# ESP32_Demo.net
KiCad netlist of a schematic drawn in Altium Designer
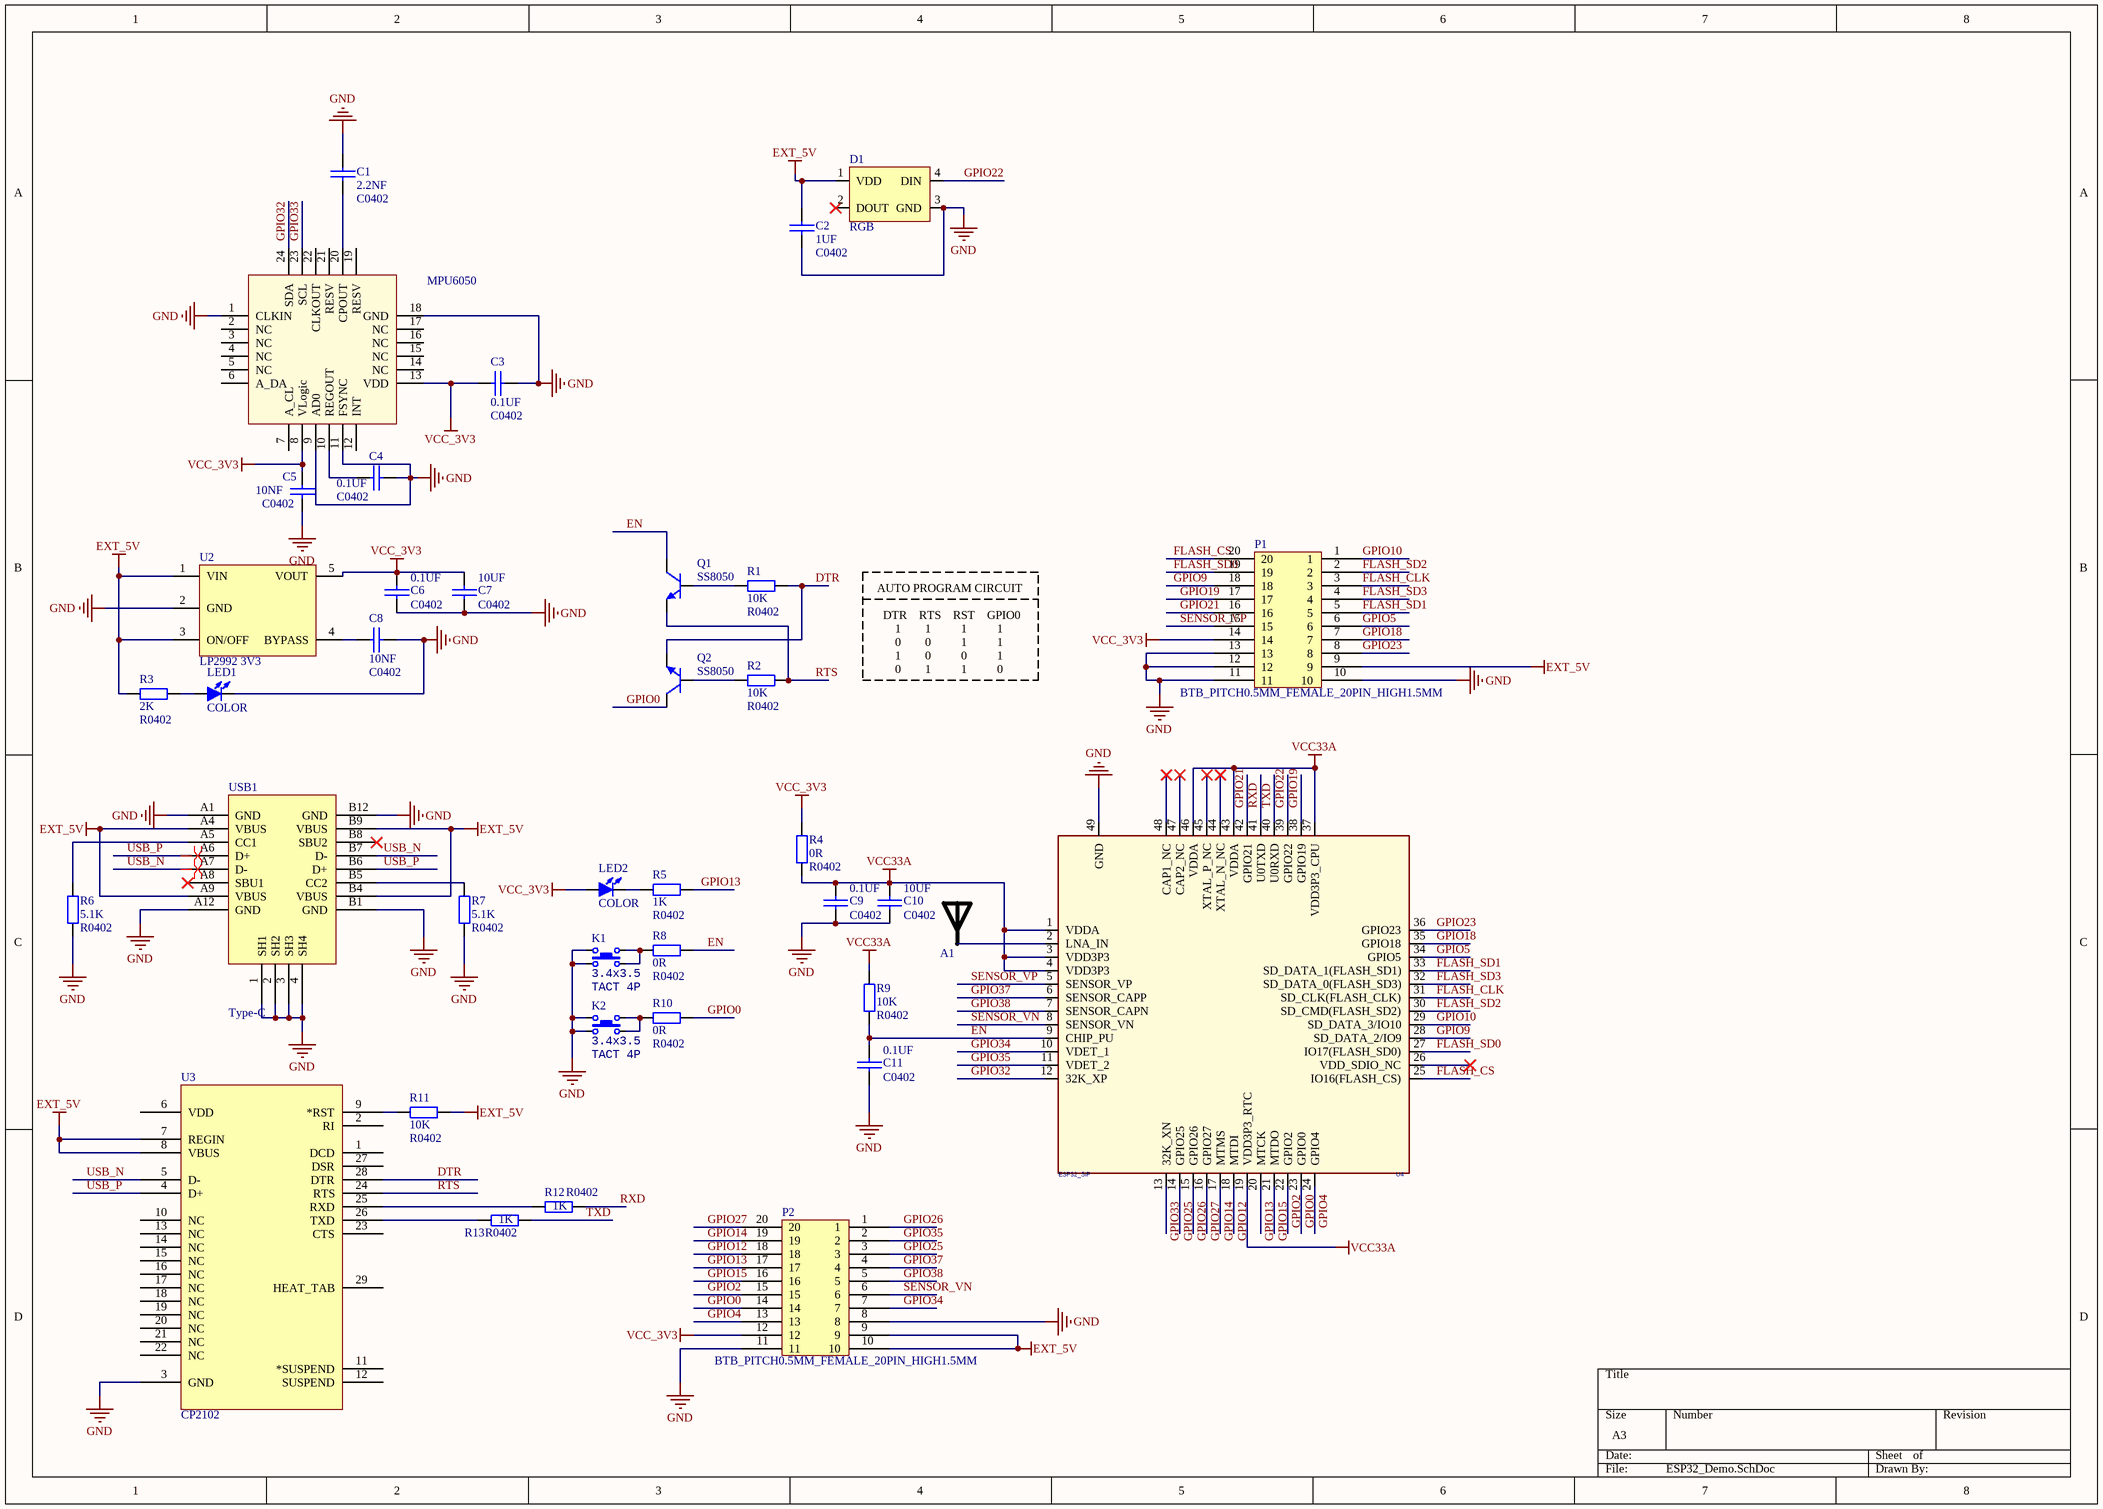
[diagram p0: ESP32_Demo.SchDoc]

(export (version "E")
  (design (tool "Eeschema 10.0.6"))
  (components
    (comp (ref "A1")
      (value "RAINSUN")
      (footprint "ANT-Rainsun-AN5120")
      (description "2.4GHz,5.1mm*2.0mm陶瓷天线，内置蓝牙WiFi")
      (libsource (lib "小器件") (part "ANT-Rainsun-AP5120"))
    )
    (comp (ref "C1")
      (value "2.2NF")
      (footprint "C0402")
      (description "0402无极性贴片电容")
      (libsource (lib "电容") (part "CAP_0402"))
    )
    (comp (ref "C2")
      (value "1UF")
      (footprint "C0402")
      (description "0402无极性贴片电容")
      (libsource (lib "电容") (part "CAP_0402"))
    )
    (comp (ref "C3")
      (value "0.1UF")
      (footprint "C0402")
      (description "0402无极性贴片电容")
      (libsource (lib "电容") (part "CAP_0402"))
    )
    (comp (ref "C4")
      (value "0.1UF")
      (footprint "C0402")
      (description "0402无极性贴片电容")
      (libsource (lib "电容") (part "CAP_0402"))
    )
    (comp (ref "C5")
      (value "10NF")
      (footprint "C0402")
      (description "0402无极性贴片电容")
      (libsource (lib "电容") (part "CAP_0402"))
    )
    (comp (ref "C6")
      (value "0.1UF")
      (footprint "C0402")
      (description "0402无极性贴片电容")
      (libsource (lib "电容") (part "CAP_0402"))
    )
    (comp (ref "C7")
      (value "10UF")
      (footprint "C0402")
      (description "0402无极性贴片电容")
      (libsource (lib "电容") (part "CAP_0402"))
    )
    (comp (ref "C8")
      (value "10NF")
      (footprint "C0402")
      (description "0402无极性贴片电容")
      (libsource (lib "电容") (part "CAP_0402"))
    )
    (comp (ref "C9")
      (value "0.1UF")
      (footprint "C0402")
      (description "0402无极性贴片电容")
      (libsource (lib "电容") (part "CAP_0402"))
    )
    (comp (ref "C10")
      (value "10UF")
      (footprint "C0402")
      (description "0402无极性贴片电容")
      (libsource (lib "电容") (part "CAP_0402"))
    )
    (comp (ref "C11")
      (value "0.1UF")
      (footprint "C0402")
      (description "0402无极性贴片电容")
      (libsource (lib "电容") (part "CAP_0402"))
    )
    (comp (ref "D1")
      (value "RGB")
      (footprint "WS2812B")
      (description "LED_5050_WS2812B")
      (libsource (lib "小器件") (part "LED_5050_WS2812B"))
    )
    (comp (ref "K1")
      (value "3.4x3.5")
      (footprint "ButtonTACT_3.5*3.55_90")
      (description "Button")
      (fields (field (name "TYPE") "TACT 4P") (field (name "Comment") "TACT 4P"))
      (libsource (lib "小器件") (part "ButtonTACT"))
    )
    (comp (ref "K2")
      (value "3.4x3.5")
      (footprint "ButtonTACT_3.5*3.55_90")
      (description "Button")
      (fields (field (name "TYPE") "TACT 4P") (field (name "Comment") "TACT 4P"))
      (libsource (lib "小器件") (part "ButtonTACT"))
    )
    (comp (ref "LED1")
      (value "COLOR")
      (footprint "LED0402")
      (description "贴片LED")
      (libsource (lib "小器件") (part "LED-SMD"))
    )
    (comp (ref "LED2")
      (value "COLOR")
      (footprint "LED0402")
      (description "贴片LED")
      (libsource (lib "小器件") (part "LED-SMD"))
    )
    (comp (ref "P1")
      (value "BTB_PITCH0.5MM_FEMALE_20PIN_HIGH1.5MM")
      (footprint "BTB_FEMALE_0.5MMPITCH_20PIN")
      (libsource (lib "接口器件") (part "BTB_PITCH0.5MM_FEMALE_20PIN_HIGH1.5MM"))
    )
    (comp (ref "P2")
      (value "BTB_PITCH0.5MM_FEMALE_20PIN_HIGH1.5MM")
      (footprint "BTB_FEMALE_0.5MMPITCH_20PIN")
      (libsource (lib "接口器件") (part "BTB_PITCH0.5MM_FEMALE_20PIN_HIGH1.5MM"))
    )
    (comp (ref "Q1")
      (value "SS8050")
      (footprint "SOT23-3N")
      (description "高频放大-NPN型")
      (libsource (lib "三极管") (part "8050-SMD"))
    )
    (comp (ref "Q2")
      (value "SS8050")
      (footprint "SOT23-3N")
      (description "高频放大-NPN型")
      (libsource (lib "三极管") (part "8050-SMD"))
    )
    (comp (ref "R1")
      (value "10K")
      (footprint "R0402")
      (description "0402电阻")
      (libsource (lib "电阻") (part "RES_0402"))
    )
    (comp (ref "R2")
      (value "10K")
      (footprint "R0402")
      (description "0402电阻")
      (libsource (lib "电阻") (part "RES_0402"))
    )
    (comp (ref "R3")
      (value "2K")
      (footprint "R0402")
      (description "0402电阻")
      (libsource (lib "电阻") (part "RES_0402"))
    )
    (comp (ref "R4")
      (value "0R")
      (footprint "R0402")
      (description "0402电阻")
      (libsource (lib "电阻") (part "RES_0402"))
    )
    (comp (ref "R5")
      (value "1K")
      (footprint "R0402")
      (description "0402电阻")
      (libsource (lib "电阻") (part "RES_0402"))
    )
    (comp (ref "R6")
      (value "5.1K")
      (footprint "R0402")
      (description "0402电阻")
      (libsource (lib "电阻") (part "RES_0402"))
    )
    (comp (ref "R7")
      (value "5.1K")
      (footprint "R0402")
      (description "0402电阻")
      (libsource (lib "电阻") (part "RES_0402"))
    )
    (comp (ref "R8")
      (value "0R")
      (footprint "R0402")
      (description "0402电阻")
      (libsource (lib "电阻") (part "RES_0402"))
    )
    (comp (ref "R9")
      (value "10K")
      (footprint "R0402")
      (description "0402电阻")
      (libsource (lib "电阻") (part "RES_0402"))
    )
    (comp (ref "R10")
      (value "0R")
      (footprint "R0402")
      (description "0402电阻")
      (libsource (lib "电阻") (part "RES_0402"))
    )
    (comp (ref "R11")
      (value "10K")
      (footprint "R0402")
      (description "0402电阻")
      (libsource (lib "电阻") (part "RES_0402"))
    )
    (comp (ref "R12")
      (value "1K")
      (footprint "R0402")
      (description "0402电阻")
      (libsource (lib "电阻") (part "RES_0402"))
    )
    (comp (ref "R13")
      (value "1K")
      (footprint "R0402")
      (description "0402电阻")
      (libsource (lib "电阻") (part "RES_0402"))
    )
    (comp (ref "U1")
      (value "MPU6050")
      (footprint "QFN-24")
      (description "六轴传感器")
      (libsource (lib "数字芯片") (part "MPU6050"))
    )
    (comp (ref "U2")
      (value "LP2992 3V3")
      (footprint "SOT23-5")
      (description "LDO")
      (libsource (lib "模拟芯片") (part "LP2992"))
    )
    (comp (ref "U3")
      (value "CP2102")
      (footprint "QFN-28")
      (description "USB转TTL")
      (libsource (lib "数字芯片") (part "CP2102"))
    )
    (comp (ref "U4")
      (value "ESP32_SIP")
      (footprint "QFN-48_7X7")
      (description "ESP32控制芯片")
      (libsource (lib "数字芯片") (part "ESP32-PICO"))
    )
    (comp (ref "USB1")
      (value "Type-C")
      (footprint "Type-C-TOP")
      (description "Type-c接口")
      (libsource (lib "接口器件") (part "USB-Type-C-TOP"))
    )
  )
  (nets
    (net (code "1") (name "/DTR") (class "Default")
      (node (ref "Q2") (pin "2") (pinfunction "E_2") (pintype "passive"))
      (node (ref "R1") (pin "2") (pinfunction "2_2") (pintype "passive"))
      (node (ref "U3") (pin "28") (pinfunction "DTR_28") (pintype "passive"))
    )
    (net (code "2") (name "/EN") (class "Default")
      (node (ref "C11") (pin "2") (pinfunction "2_2") (pintype "passive"))
      (node (ref "Q1") (pin "3") (pinfunction "C_3") (pintype "passive"))
      (node (ref "R8") (pin "2") (pinfunction "2_2") (pintype "passive"))
      (node (ref "R9") (pin "2") (pinfunction "2_2") (pintype "passive"))
      (node (ref "U4") (pin "9") (pinfunction "CHIP_PU_9") (pintype "passive"))
    )
    (net (code "3") (name "/FLASH_CLK") (class "Default")
      (node (ref "P1") (pin "3") (pinfunction "3_3") (pintype "passive"))
      (node (ref "U4") (pin "31") (pinfunction "SD_CLK(FLASH_CLK)_31") (pintype "passive"))
    )
    (net (code "4") (name "/FLASH_CS") (class "Default")
      (node (ref "P1") (pin "20") (pinfunction "20_20") (pintype "passive"))
      (node (ref "U4") (pin "25") (pinfunction "IO16(FLASH_CS)_25") (pintype "passive"))
    )
    (net (code "5") (name "/FLASH_SD0") (class "Default")
      (node (ref "P1") (pin "19") (pinfunction "19_19") (pintype "passive"))
      (node (ref "U4") (pin "27") (pinfunction "IO17(FLASH_SD0)_27") (pintype "passive"))
    )
    (net (code "6") (name "/FLASH_SD1") (class "Default")
      (node (ref "P1") (pin "5") (pinfunction "5_5") (pintype "passive"))
      (node (ref "U4") (pin "33") (pinfunction "SD_DATA_1(FLASH_SD1)_33") (pintype "passive"))
    )
    (net (code "7") (name "/FLASH_SD2") (class "Default")
      (node (ref "P1") (pin "2") (pinfunction "2_2") (pintype "passive"))
      (node (ref "U4") (pin "30") (pinfunction "SD_CMD(FLASH_SD2)_30") (pintype "passive"))
    )
    (net (code "8") (name "/FLASH_SD3") (class "Default")
      (node (ref "P1") (pin "4") (pinfunction "4_4") (pintype "passive"))
      (node (ref "U4") (pin "32") (pinfunction "SD_DATA_0(FLASH_SD3)_32") (pintype "passive"))
    )
    (net (code "9") (name "/GPIO0") (class "Default")
      (node (ref "P2") (pin "14") (pinfunction "14_14") (pintype "passive"))
      (node (ref "Q2") (pin "3") (pinfunction "C_3") (pintype "passive"))
      (node (ref "R10") (pin "2") (pinfunction "2_2") (pintype "passive"))
      (node (ref "U4") (pin "23") (pinfunction "GPIO0_23") (pintype "passive"))
    )
    (net (code "10") (name "/GPIO2") (class "Default")
      (node (ref "P2") (pin "15") (pinfunction "15_15") (pintype "passive"))
      (node (ref "U4") (pin "22") (pinfunction "GPIO2_22") (pintype "passive"))
    )
    (net (code "11") (name "/GPIO4") (class "Default")
      (node (ref "P2") (pin "13") (pinfunction "13_13") (pintype "passive"))
      (node (ref "U4") (pin "24") (pinfunction "GPIO4_24") (pintype "passive"))
    )
    (net (code "12") (name "/GPIO5") (class "Default")
      (node (ref "P1") (pin "6") (pinfunction "6_6") (pintype "passive"))
      (node (ref "U4") (pin "34") (pinfunction "GPIO5_34") (pintype "passive"))
    )
    (net (code "13") (name "/GPIO9") (class "Default")
      (node (ref "P1") (pin "18") (pinfunction "18_18") (pintype "passive"))
      (node (ref "U4") (pin "28") (pinfunction "SD_DATA_2/IO9_28") (pintype "passive"))
    )
    (net (code "14") (name "/GPIO10") (class "Default")
      (node (ref "P1") (pin "1") (pinfunction "1_1") (pintype "passive"))
      (node (ref "U4") (pin "29") (pinfunction "SD_DATA_3/IO10_29") (pintype "passive"))
    )
    (net (code "15") (name "/GPIO12") (class "Default")
      (node (ref "P2") (pin "18") (pinfunction "18_18") (pintype "passive"))
      (node (ref "U4") (pin "18") (pinfunction "MTDI_18") (pintype "passive"))
    )
    (net (code "16") (name "/GPIO13") (class "Default")
      (node (ref "P2") (pin "17") (pinfunction "17_17") (pintype "passive"))
      (node (ref "R5") (pin "1") (pinfunction "1_1") (pintype "passive"))
      (node (ref "U4") (pin "20") (pinfunction "MTCK_20") (pintype "passive"))
    )
    (net (code "17") (name "/GPIO14") (class "Default")
      (node (ref "P2") (pin "19") (pinfunction "19_19") (pintype "passive"))
      (node (ref "U4") (pin "17") (pinfunction "MTMS_17") (pintype "passive"))
    )
    (net (code "18") (name "/GPIO15") (class "Default")
      (node (ref "P2") (pin "16") (pinfunction "16_16") (pintype "passive"))
      (node (ref "U4") (pin "21") (pinfunction "MTDO_21") (pintype "passive"))
    )
    (net (code "19") (name "/GPIO18") (class "Default")
      (node (ref "P1") (pin "7") (pinfunction "7_7") (pintype "passive"))
      (node (ref "U4") (pin "35") (pinfunction "GPIO18_35") (pintype "passive"))
    )
    (net (code "20") (name "/GPIO19") (class "Default")
      (node (ref "P1") (pin "17") (pinfunction "17_17") (pintype "passive"))
      (node (ref "U4") (pin "38") (pinfunction "GPIO19_38") (pintype "passive"))
    )
    (net (code "21") (name "/GPIO21") (class "Default")
      (node (ref "P1") (pin "16") (pinfunction "16_16") (pintype "passive"))
      (node (ref "U4") (pin "42") (pinfunction "GPIO21_42") (pintype "passive"))
    )
    (net (code "22") (name "/GPIO22") (class "Default")
      (node (ref "D1") (pin "4") (pinfunction "DIN_4") (pintype "passive"))
      (node (ref "U4") (pin "39") (pinfunction "GPIO22_39") (pintype "passive"))
    )
    (net (code "23") (name "/GPIO23") (class "Default")
      (node (ref "P1") (pin "8") (pinfunction "8_8") (pintype "passive"))
      (node (ref "U4") (pin "36") (pinfunction "GPIO23_36") (pintype "passive"))
    )
    (net (code "24") (name "/GPIO25") (class "Default")
      (node (ref "P2") (pin "3") (pinfunction "3_3") (pintype "passive"))
      (node (ref "U4") (pin "14") (pinfunction "GPIO25_14") (pintype "passive"))
    )
    (net (code "25") (name "/GPIO26") (class "Default")
      (node (ref "P2") (pin "1") (pinfunction "1_1") (pintype "passive"))
      (node (ref "U4") (pin "15") (pinfunction "GPIO26_15") (pintype "passive"))
    )
    (net (code "26") (name "/GPIO27") (class "Default")
      (node (ref "P2") (pin "20") (pinfunction "20_20") (pintype "passive"))
      (node (ref "U4") (pin "16") (pinfunction "GPIO27_16") (pintype "passive"))
    )
    (net (code "27") (name "/GPIO32") (class "Default")
      (node (ref "U1") (pin "24") (pinfunction "SDA_24") (pintype "passive"))
      (node (ref "U4") (pin "12") (pinfunction "32K_XP_12") (pintype "passive"))
    )
    (net (code "28") (name "/GPIO33") (class "Default")
      (node (ref "U1") (pin "23") (pinfunction "SCL_23") (pintype "passive"))
      (node (ref "U4") (pin "13") (pinfunction "32K_XN_13") (pintype "passive"))
    )
    (net (code "29") (name "/GPIO34") (class "Default")
      (node (ref "P2") (pin "7") (pinfunction "7_7") (pintype "passive"))
      (node (ref "U4") (pin "10") (pinfunction "VDET_1_10") (pintype "passive"))
    )
    (net (code "30") (name "/GPIO35") (class "Default")
      (node (ref "P2") (pin "2") (pinfunction "2_2") (pintype "passive"))
      (node (ref "U4") (pin "11") (pinfunction "VDET_2_11") (pintype "passive"))
    )
    (net (code "31") (name "/GPIO37") (class "Default")
      (node (ref "P2") (pin "4") (pinfunction "4_4") (pintype "passive"))
      (node (ref "U4") (pin "6") (pinfunction "SENSOR_CAPP_6") (pintype "passive"))
    )
    (net (code "32") (name "/GPIO38") (class "Default")
      (node (ref "P2") (pin "5") (pinfunction "5_5") (pintype "passive"))
      (node (ref "U4") (pin "7") (pinfunction "SENSOR_CAPN_7") (pintype "passive"))
    )
    (net (code "33") (name "/RTS") (class "Default")
      (node (ref "Q1") (pin "2") (pinfunction "E_2") (pintype "passive"))
      (node (ref "R2") (pin "2") (pinfunction "2_2") (pintype "passive"))
      (node (ref "U3") (pin "24") (pinfunction "RTS_24") (pintype "passive"))
    )
    (net (code "34") (name "/RXD") (class "Default")
      (node (ref "R12") (pin "2") (pinfunction "2_2") (pintype "passive"))
      (node (ref "U4") (pin "41") (pinfunction "U0TXD_41") (pintype "power_in"))
    )
    (net (code "35") (name "/SENSOR_VN") (class "Default")
      (node (ref "P2") (pin "6") (pinfunction "6_6") (pintype "passive"))
      (node (ref "U4") (pin "8") (pinfunction "SENSOR_VN_8") (pintype "passive"))
    )
    (net (code "36") (name "/SENSOR_VP") (class "Default")
      (node (ref "P1") (pin "15") (pinfunction "15_15") (pintype "passive"))
      (node (ref "U4") (pin "5") (pinfunction "SENSOR_VP_5") (pintype "passive"))
    )
    (net (code "37") (name "/TXD") (class "Default")
      (node (ref "R13") (pin "2") (pinfunction "2_2") (pintype "passive"))
      (node (ref "U4") (pin "40") (pinfunction "U0RXD_40") (pintype "power_in"))
    )
    (net (code "38") (name "/USB_N") (class "Default")
      (node (ref "U3") (pin "5") (pinfunction "D-_5") (pintype "passive"))
      (node (ref "USB1") (pin "A7") (pinfunction "D-_A7") (pintype "passive"))
      (node (ref "USB1") (pin "B7") (pinfunction "D-_B7") (pintype "passive"))
    )
    (net (code "39") (name "/USB_P") (class "Default")
      (node (ref "U3") (pin "4") (pinfunction "D+_4") (pintype "passive"))
      (node (ref "USB1") (pin "A6") (pinfunction "D+_A6") (pintype "passive"))
      (node (ref "USB1") (pin "B6") (pinfunction "D+_B6") (pintype "passive"))
    )
    (net (code "40") (name "EXT_5V") (class "Default")
      (node (ref "C2") (pin "1") (pinfunction "1_1") (pintype "passive"))
      (node (ref "D1") (pin "1") (pinfunction "VDD_1") (pintype "passive"))
      (node (ref "P1") (pin "9") (pinfunction "9_9") (pintype "passive"))
      (node (ref "P2") (pin "10") (pinfunction "10_10") (pintype "passive"))
      (node (ref "P2") (pin "9") (pinfunction "9_9") (pintype "passive"))
      (node (ref "R11") (pin "2") (pinfunction "2_2") (pintype "passive"))
      (node (ref "R3") (pin "2") (pinfunction "2_2") (pintype "passive"))
      (node (ref "U2") (pin "1") (pinfunction "VIN_1") (pintype "passive"))
      (node (ref "U2") (pin "3") (pinfunction "ON/OFF_3") (pintype "passive"))
      (node (ref "U3") (pin "7") (pinfunction "REGIN_7") (pintype "passive"))
      (node (ref "U3") (pin "8") (pinfunction "VBUS_8") (pintype "passive"))
      (node (ref "USB1") (pin "A4") (pinfunction "VBUS_A4") (pintype "passive"))
      (node (ref "USB1") (pin "A9") (pinfunction "VBUS_A9") (pintype "passive"))
      (node (ref "USB1") (pin "B4") (pinfunction "VBUS_B4") (pintype "passive"))
      (node (ref "USB1") (pin "B9") (pinfunction "VBUS_B9") (pintype "passive"))
    )
    (net (code "41") (name "GND") (class "Default")
      (node (ref "C1") (pin "1") (pinfunction "1_1") (pintype "passive"))
      (node (ref "C10") (pin "1") (pinfunction "1_1") (pintype "passive"))
      (node (ref "C11") (pin "1") (pinfunction "1_1") (pintype "passive"))
      (node (ref "C2") (pin "2") (pinfunction "2_2") (pintype "passive"))
      (node (ref "C3") (pin "1") (pinfunction "1_1") (pintype "passive"))
      (node (ref "C4") (pin "2") (pinfunction "2_2") (pintype "passive"))
      (node (ref "C5") (pin "2") (pinfunction "2_2") (pintype "passive"))
      (node (ref "C6") (pin "1") (pinfunction "1_1") (pintype "passive"))
      (node (ref "C7") (pin "1") (pinfunction "1_1") (pintype "passive"))
      (node (ref "C8") (pin "2") (pinfunction "2_2") (pintype "passive"))
      (node (ref "C9") (pin "1") (pinfunction "1_1") (pintype "passive"))
      (node (ref "D1") (pin "3") (pinfunction "GND_3") (pintype "passive"))
      (node (ref "K1") (pin "1") (pinfunction "1_1") (pintype "passive"))
      (node (ref "K1") (pin "3") (pinfunction "3_3") (pintype "passive"))
      (node (ref "K2") (pin "1") (pinfunction "1_1") (pintype "passive"))
      (node (ref "K2") (pin "3") (pinfunction "3_3") (pintype "passive"))
      (node (ref "LED1") (pin "2") (pinfunction "K_2") (pintype "passive"))
      (node (ref "P1") (pin "10") (pinfunction "10_10") (pintype "passive"))
      (node (ref "P1") (pin "11") (pinfunction "11_11") (pintype "passive"))
      (node (ref "P1") (pin "12") (pinfunction "12_12") (pintype "passive"))
      (node (ref "P1") (pin "13") (pinfunction "13_13") (pintype "passive"))
      (node (ref "P2") (pin "11") (pinfunction "11_11") (pintype "passive"))
      (node (ref "P2") (pin "8") (pinfunction "8_8") (pintype "passive"))
      (node (ref "R6") (pin "2") (pinfunction "2_2") (pintype "passive"))
      (node (ref "R7") (pin "2") (pinfunction "2_2") (pintype "passive"))
      (node (ref "U1") (pin "1") (pinfunction "CLKIN_1") (pintype "passive"))
      (node (ref "U1") (pin "11") (pinfunction "FSYNC_11") (pintype "passive"))
      (node (ref "U1") (pin "18") (pinfunction "GND_18") (pintype "passive"))
      (node (ref "U1") (pin "9") (pinfunction "AD0_9") (pintype "passive"))
      (node (ref "U2") (pin "2") (pinfunction "GND_2") (pintype "passive"))
      (node (ref "U3") (pin "3") (pinfunction "GND_3") (pintype "passive"))
      (node (ref "U4") (pin "49") (pinfunction "GND_49") (pintype "power_in"))
      (node (ref "USB1") (pin "1") (pinfunction "SH1_1") (pintype "passive"))
      (node (ref "USB1") (pin "2") (pinfunction "SH2_2") (pintype "passive"))
      (node (ref "USB1") (pin "3") (pinfunction "SH3_3") (pintype "passive"))
      (node (ref "USB1") (pin "4") (pinfunction "SH4_4") (pintype "passive"))
      (node (ref "USB1") (pin "A1") (pinfunction "GND_A1") (pintype "passive"))
      (node (ref "USB1") (pin "A12") (pinfunction "GND_A12") (pintype "passive"))
      (node (ref "USB1") (pin "B1") (pinfunction "GND_B1") (pintype "passive"))
      (node (ref "USB1") (pin "B12") (pinfunction "GND_B12") (pintype "passive"))
    )
    (net (code "42") (name "Net-(K1-Pad2)") (class "Default")
      (node (ref "K1") (pin "2") (pinfunction "2_2") (pintype "passive"))
      (node (ref "K1") (pin "4") (pinfunction "4_4") (pintype "passive"))
      (node (ref "R8") (pin "1") (pinfunction "1_1") (pintype "passive"))
    )
    (net (code "43") (name "Net-(K2-Pad2)") (class "Default")
      (node (ref "K2") (pin "2") (pinfunction "2_2") (pintype "passive"))
      (node (ref "K2") (pin "4") (pinfunction "4_4") (pintype "passive"))
      (node (ref "R10") (pin "1") (pinfunction "1_1") (pintype "passive"))
    )
    (net (code "44") (name "Net-(LED1-A)") (class "Default")
      (node (ref "LED1") (pin "1") (pinfunction "A_1") (pintype "passive"))
      (node (ref "R3") (pin "1") (pinfunction "1_1") (pintype "passive"))
    )
    (net (code "45") (name "Net-(LED2-K)") (class "Default")
      (node (ref "LED2") (pin "2") (pinfunction "K_2") (pintype "passive"))
      (node (ref "R5") (pin "2") (pinfunction "2_2") (pintype "passive"))
    )
    (net (code "46") (name "Net-(Q1-B)") (class "Default")
      (node (ref "Q1") (pin "1") (pinfunction "B_1") (pintype "passive"))
      (node (ref "R1") (pin "1") (pinfunction "1_1") (pintype "passive"))
    )
    (net (code "47") (name "Net-(Q2-B)") (class "Default")
      (node (ref "Q2") (pin "1") (pinfunction "B_1") (pintype "passive"))
      (node (ref "R2") (pin "1") (pinfunction "1_1") (pintype "passive"))
    )
    (net (code "48") (name "Net-(U1-CPOUT)") (class "Default")
      (node (ref "C1") (pin "2") (pinfunction "2_2") (pintype "passive"))
      (node (ref "U1") (pin "20") (pinfunction "CPOUT_20") (pintype "passive"))
    )
    (net (code "49") (name "Net-(U1-REGOUT)") (class "Default")
      (node (ref "C4") (pin "1") (pinfunction "1_1") (pintype "passive"))
      (node (ref "U1") (pin "10") (pinfunction "REGOUT_10") (pintype "passive"))
    )
    (net (code "50") (name "Net-(U2-BYPASS)") (class "Default")
      (node (ref "C8") (pin "1") (pinfunction "1_1") (pintype "passive"))
      (node (ref "U2") (pin "4") (pinfunction "BYPASS_4") (pintype "passive"))
    )
    (net (code "51") (name "Net-(U3-*RST)") (class "Default")
      (node (ref "R11") (pin "1") (pinfunction "1_1") (pintype "passive"))
      (node (ref "U3") (pin "9") (pinfunction "*RST_9") (pintype "passive"))
    )
    (net (code "52") (name "Net-(U3-RXD)") (class "Default")
      (node (ref "R12") (pin "1") (pinfunction "1_1") (pintype "passive"))
      (node (ref "U3") (pin "25") (pinfunction "RXD_25") (pintype "passive"))
    )
    (net (code "53") (name "Net-(U3-TXD)") (class "Default")
      (node (ref "R13") (pin "1") (pinfunction "1_1") (pintype "passive"))
      (node (ref "U3") (pin "26") (pinfunction "TXD_26") (pintype "passive"))
    )
    (net (code "54") (name "Net-(U4-LNA_IN)") (class "Default")
      (node (ref "A1") (pin "1") (pinfunction "1_1") (pintype "passive"))
      (node (ref "U4") (pin "2") (pinfunction "LNA_IN_2") (pintype "passive"))
    )
    (net (code "55") (name "Net-(USB1-CC1)") (class "Default")
      (node (ref "R6") (pin "1") (pinfunction "1_1") (pintype "passive"))
      (node (ref "USB1") (pin "A5") (pinfunction "CC1_A5") (pintype "passive"))
    )
    (net (code "56") (name "Net-(USB1-CC2)") (class "Default")
      (node (ref "R7") (pin "1") (pinfunction "1_1") (pintype "passive"))
      (node (ref "USB1") (pin "B5") (pinfunction "CC2_B5") (pintype "passive"))
    )
    (net (code "57") (name "VCC33A") (class "Default")
      (node (ref "C10") (pin "2") (pinfunction "2_2") (pintype "passive"))
      (node (ref "C9") (pin "2") (pinfunction "2_2") (pintype "passive"))
      (node (ref "R4") (pin "2") (pinfunction "2_2") (pintype "passive"))
      (node (ref "R9") (pin "1") (pinfunction "1_1") (pintype "passive"))
      (node (ref "U4") (pin "1") (pinfunction "VDDA_1") (pintype "power_in"))
      (node (ref "U4") (pin "19") (pinfunction "VDD3P3_RTC_19") (pintype "power_in"))
      (node (ref "U4") (pin "3") (pinfunction "VDD3P3_3") (pintype "power_in"))
      (node (ref "U4") (pin "37") (pinfunction "VDD3P3_CPU_37") (pintype "power_in"))
      (node (ref "U4") (pin "4") (pinfunction "VDD3P3_4") (pintype "power_in"))
      (node (ref "U4") (pin "43") (pinfunction "VDDA_43") (pintype "power_in"))
      (node (ref "U4") (pin "46") (pinfunction "VDDA_46") (pintype "power_in"))
    )
    (net (code "58") (name "VCC_3V3") (class "Default")
      (node (ref "C3") (pin "2") (pinfunction "2_2") (pintype "passive"))
      (node (ref "C5") (pin "1") (pinfunction "1_1") (pintype "passive"))
      (node (ref "C6") (pin "2") (pinfunction "2_2") (pintype "passive"))
      (node (ref "C7") (pin "2") (pinfunction "2_2") (pintype "passive"))
      (node (ref "LED2") (pin "1") (pinfunction "A_1") (pintype "passive"))
      (node (ref "P1") (pin "14") (pinfunction "14_14") (pintype "passive"))
      (node (ref "P2") (pin "12") (pinfunction "12_12") (pintype "passive"))
      (node (ref "R4") (pin "1") (pinfunction "1_1") (pintype "passive"))
      (node (ref "U1") (pin "13") (pinfunction "VDD_13") (pintype "passive"))
      (node (ref "U1") (pin "8") (pinfunction "VLogic_8") (pintype "passive"))
      (node (ref "U2") (pin "5") (pinfunction "VOUT_5") (pintype "passive"))
    )
    (net (code "59") (name "unconnected-(D1-DOUT-Pad2)") (class "Default")
      (node (ref "D1") (pin "2") (pinfunction "DOUT_2") (pintype "passive+no_connect"))
    )
    (net (code "60") (name "unconnected-(U1-A_CL-Pad7)") (class "Default")
      (node (ref "U1") (pin "7") (pinfunction "A_CL_7") (pintype "passive"))
    )
    (net (code "61") (name "unconnected-(U1-A_DA-Pad6)") (class "Default")
      (node (ref "U1") (pin "6") (pinfunction "A_DA_6") (pintype "passive"))
    )
    (net (code "62") (name "unconnected-(U1-CLKOUT-Pad22)") (class "Default")
      (node (ref "U1") (pin "22") (pinfunction "CLKOUT_22") (pintype "passive"))
    )
    (net (code "63") (name "unconnected-(U1-INT-Pad12)") (class "Default")
      (node (ref "U1") (pin "12") (pinfunction "INT_12") (pintype "passive"))
    )
    (net (code "64") (name "unconnected-(U1-NC-Pad2)") (class "Default")
      (node (ref "U1") (pin "2") (pinfunction "NC_2") (pintype "passive"))
    )
    (net (code "65") (name "unconnected-(U1-NC-Pad3)") (class "Default")
      (node (ref "U1") (pin "3") (pinfunction "NC_3") (pintype "passive"))
    )
    (net (code "66") (name "unconnected-(U1-NC-Pad4)") (class "Default")
      (node (ref "U1") (pin "4") (pinfunction "NC_4") (pintype "passive"))
    )
    (net (code "67") (name "unconnected-(U1-NC-Pad5)") (class "Default")
      (node (ref "U1") (pin "5") (pinfunction "NC_5") (pintype "passive"))
    )
    (net (code "68") (name "unconnected-(U1-NC-Pad14)") (class "Default")
      (node (ref "U1") (pin "14") (pinfunction "NC_14") (pintype "passive"))
    )
    (net (code "69") (name "unconnected-(U1-NC-Pad15)") (class "Default")
      (node (ref "U1") (pin "15") (pinfunction "NC_15") (pintype "passive"))
    )
    (net (code "70") (name "unconnected-(U1-NC-Pad16)") (class "Default")
      (node (ref "U1") (pin "16") (pinfunction "NC_16") (pintype "passive"))
    )
    (net (code "71") (name "unconnected-(U1-NC-Pad17)") (class "Default")
      (node (ref "U1") (pin "17") (pinfunction "NC_17") (pintype "passive"))
    )
    (net (code "72") (name "unconnected-(U1-RESV-Pad19)") (class "Default")
      (node (ref "U1") (pin "19") (pinfunction "RESV_19") (pintype "passive"))
    )
    (net (code "73") (name "unconnected-(U1-RESV-Pad21)") (class "Default")
      (node (ref "U1") (pin "21") (pinfunction "RESV_21") (pintype "passive"))
    )
    (net (code "74") (name "unconnected-(U3-*SUSPEND-Pad11)") (class "Default")
      (node (ref "U3") (pin "11") (pinfunction "*SUSPEND_11") (pintype "passive"))
    )
    (net (code "75") (name "unconnected-(U3-CTS-Pad23)") (class "Default")
      (node (ref "U3") (pin "23") (pinfunction "CTS_23") (pintype "passive"))
    )
    (net (code "76") (name "unconnected-(U3-DCD-Pad1)") (class "Default")
      (node (ref "U3") (pin "1") (pinfunction "DCD_1") (pintype "passive"))
    )
    (net (code "77") (name "unconnected-(U3-DSR-Pad27)") (class "Default")
      (node (ref "U3") (pin "27") (pinfunction "DSR_27") (pintype "passive"))
    )
    (net (code "78") (name "unconnected-(U3-HEAT_TAB-Pad29)") (class "Default")
      (node (ref "U3") (pin "29") (pinfunction "HEAT_TAB_29") (pintype "passive"))
    )
    (net (code "79") (name "unconnected-(U3-NC-Pad10)") (class "Default")
      (node (ref "U3") (pin "10") (pinfunction "NC_10") (pintype "passive"))
    )
    (net (code "80") (name "unconnected-(U3-NC-Pad13)") (class "Default")
      (node (ref "U3") (pin "13") (pinfunction "NC_13") (pintype "passive"))
    )
    (net (code "81") (name "unconnected-(U3-NC-Pad14)") (class "Default")
      (node (ref "U3") (pin "14") (pinfunction "NC_14") (pintype "passive"))
    )
    (net (code "82") (name "unconnected-(U3-NC-Pad15)") (class "Default")
      (node (ref "U3") (pin "15") (pinfunction "NC_15") (pintype "passive"))
    )
    (net (code "83") (name "unconnected-(U3-NC-Pad16)") (class "Default")
      (node (ref "U3") (pin "16") (pinfunction "NC_16") (pintype "passive"))
    )
    (net (code "84") (name "unconnected-(U3-NC-Pad17)") (class "Default")
      (node (ref "U3") (pin "17") (pinfunction "NC_17") (pintype "passive"))
    )
    (net (code "85") (name "unconnected-(U3-NC-Pad18)") (class "Default")
      (node (ref "U3") (pin "18") (pinfunction "NC_18") (pintype "passive"))
    )
    (net (code "86") (name "unconnected-(U3-NC-Pad19)") (class "Default")
      (node (ref "U3") (pin "19") (pinfunction "NC_19") (pintype "passive"))
    )
    (net (code "87") (name "unconnected-(U3-NC-Pad20)") (class "Default")
      (node (ref "U3") (pin "20") (pinfunction "NC_20") (pintype "passive"))
    )
    (net (code "88") (name "unconnected-(U3-NC-Pad21)") (class "Default")
      (node (ref "U3") (pin "21") (pinfunction "NC_21") (pintype "passive"))
    )
    (net (code "89") (name "unconnected-(U3-NC-Pad22)") (class "Default")
      (node (ref "U3") (pin "22") (pinfunction "NC_22") (pintype "passive"))
    )
    (net (code "90") (name "unconnected-(U3-RI-Pad2)") (class "Default")
      (node (ref "U3") (pin "2") (pinfunction "RI_2") (pintype "passive"))
    )
    (net (code "91") (name "unconnected-(U3-SUSPEND-Pad12)") (class "Default")
      (node (ref "U3") (pin "12") (pinfunction "SUSPEND_12") (pintype "passive"))
    )
    (net (code "92") (name "unconnected-(U3-VDD-Pad6)") (class "Default")
      (node (ref "U3") (pin "6") (pinfunction "VDD_6") (pintype "passive"))
    )
    (net (code "93") (name "unconnected-(U4-CAP1_NC-Pad48)") (class "Default")
      (node (ref "U4") (pin "48") (pinfunction "CAP1_NC_48") (pintype "passive+no_connect"))
    )
    (net (code "94") (name "unconnected-(U4-CAP2_NC-Pad47)") (class "Default")
      (node (ref "U4") (pin "47") (pinfunction "CAP2_NC_47") (pintype "passive+no_connect"))
    )
    (net (code "95") (name "unconnected-(U4-VDD_SDIO_NC-Pad26)") (class "Default")
      (node (ref "U4") (pin "26") (pinfunction "VDD_SDIO_NC_26") (pintype "passive+no_connect"))
    )
    (net (code "96") (name "unconnected-(U4-XTAL_N_NC-Pad44)") (class "Default")
      (node (ref "U4") (pin "44") (pinfunction "XTAL_N_NC_44") (pintype "passive+no_connect"))
    )
    (net (code "97") (name "unconnected-(U4-XTAL_P_NC-Pad45)") (class "Default")
      (node (ref "U4") (pin "45") (pinfunction "XTAL_P_NC_45") (pintype "passive+no_connect"))
    )
    (net (code "98") (name "unconnected-(USB1-SBU1-PadA8)") (class "Default")
      (node (ref "USB1") (pin "A8") (pinfunction "SBU1_A8") (pintype "passive+no_connect"))
    )
    (net (code "99") (name "unconnected-(USB1-SBU2-PadB8)") (class "Default")
      (node (ref "USB1") (pin "B8") (pinfunction "SBU2_B8") (pintype "passive+no_connect"))
    )
  )
)
